# 6_-MCU_CONNECTORS.net
KiCad netlist of a schematic drawn in Altium Designer
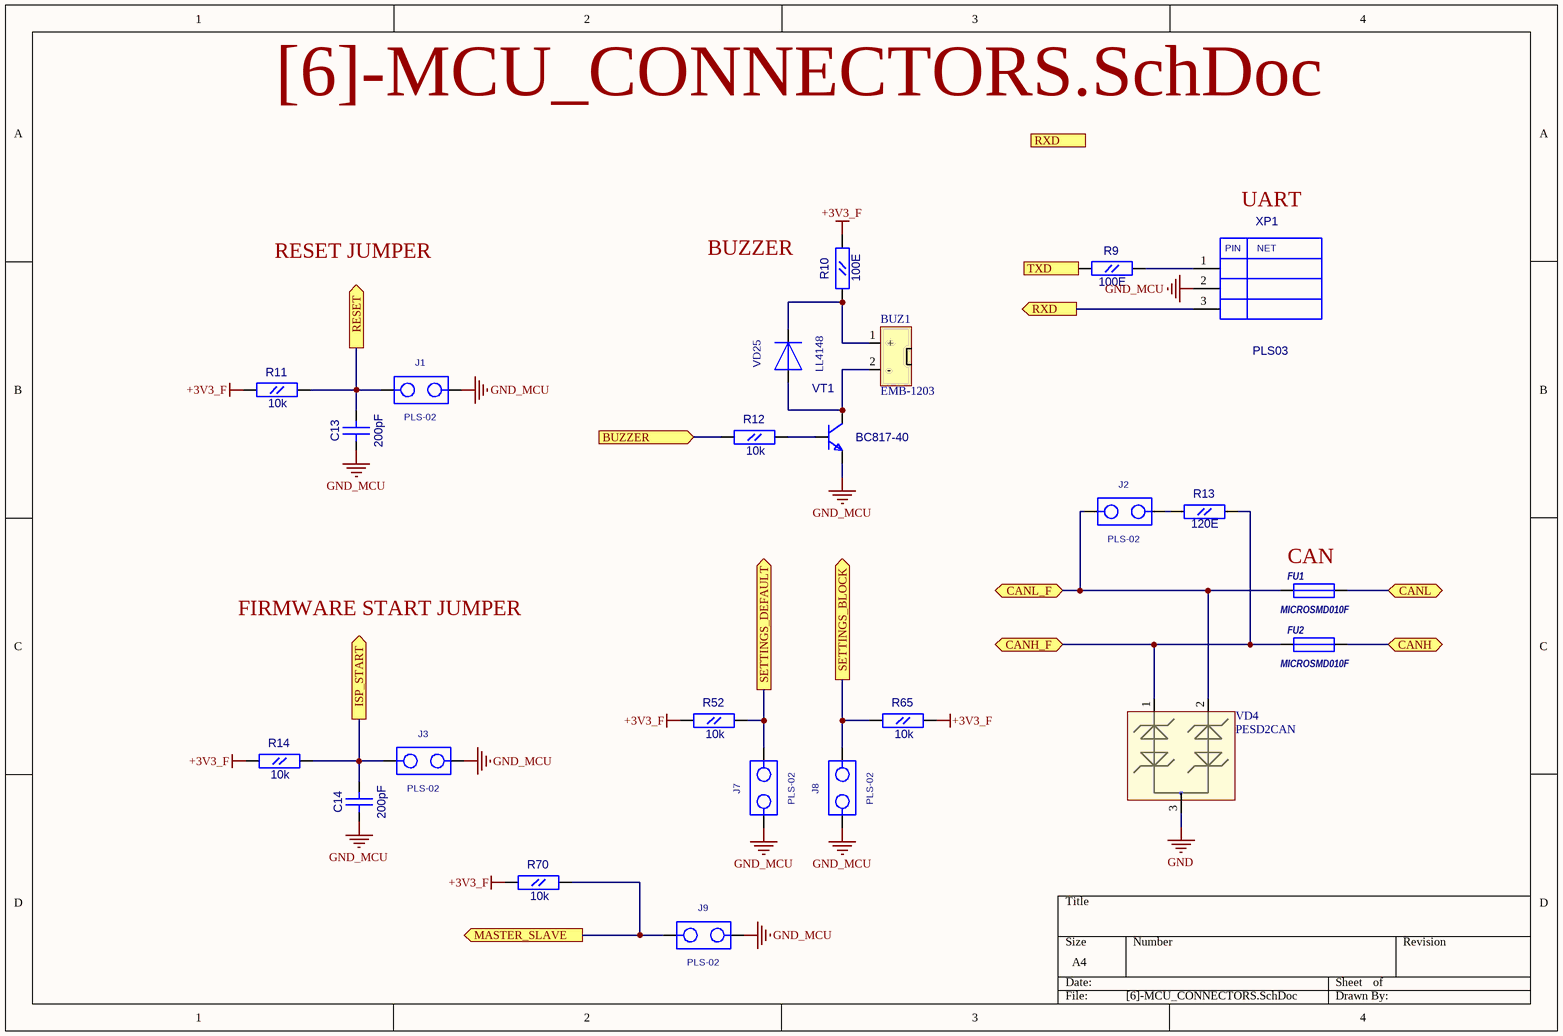
[diagram p0: [6]-MCU_CONNECTORS.SchDoc]

(export (version "E")
  (design (tool "Eeschema 10.0.6"))
  (components
    (comp (ref "BUZ1")
      (value "EMB-1203")
      (footprint "BUZZER_12")
      (description "Buzzer diameter 12mm 3V")
      (libsource (lib "fizik_lib") (part "EMB-1203"))
    )
    (comp (ref "C13")
      (value "200pF")
      (footprint "CC0603")
      (description "CC0603")
      (libsource (lib "gprs_modem_2") (part "CC0603"))
    )
    (comp (ref "C14")
      (value "200pF")
      (footprint "CC0603")
      (description "CC0603")
      (libsource (lib "gprs_modem_2") (part "CC0603"))
    )
    (comp (ref "FU1")
      (value "MICROSMD010F")
      (footprint "RC1210")
      (description "MICROSMD")
      (libsource (lib "gprs_modem_2") (part "MICROSMD"))
    )
    (comp (ref "FU2")
      (value "MICROSMD010F")
      (footprint "RC1210")
      (description "MICROSMD")
      (libsource (lib "gprs_modem_2") (part "MICROSMD"))
    )
    (comp (ref "J1") (value "PLS-02") (footprint "PLS-02") (libsource (lib "gprs_modem_2") (part "PLS-02")))
    (comp (ref "J2") (value "PLS-02") (footprint "PLS-02") (libsource (lib "fizik_lib") (part "PLS-02")))
    (comp (ref "J3") (value "PLS-02") (footprint "PLS-02") (libsource (lib "gprs_modem_2") (part "PLS-02")))
    (comp (ref "J7") (value "PLS-02") (footprint "PLS-02") (libsource (lib "gprs_modem_2") (part "PLS-02")))
    (comp (ref "J8") (value "PLS-02") (footprint "PLS-02") (libsource (lib "gprs_modem_2") (part "PLS-02")))
    (comp (ref "J9") (value "PLS-02") (footprint "PLS-02") (libsource (lib "gprs_modem_2") (part "PLS-02")))
    (comp (ref "R9")
      (value "100E")
      (footprint "RC0603")
      (description "RC0603")
      (libsource (lib "gprs_modem_2") (part "RC0603"))
    )
    (comp (ref "R10")
      (value "100E")
      (footprint "RC0603")
      (description "RC0603")
      (libsource (lib "gprs_modem_2") (part "RC0603"))
    )
    (comp (ref "R11")
      (value "10k")
      (footprint "RC0603")
      (description "RC0603")
      (libsource (lib "gprs_modem_2") (part "RC0603"))
    )
    (comp (ref "R12")
      (value "10k")
      (footprint "RC0603")
      (description "RC0603")
      (libsource (lib "gprs_modem_2") (part "RC0603"))
    )
    (comp (ref "R13")
      (value "120E")
      (footprint "RC0805")
      (description "RC0805")
      (libsource (lib "fizik_lib") (part "RC0805"))
    )
    (comp (ref "R14")
      (value "10k")
      (footprint "RC0603")
      (description "RC0603")
      (libsource (lib "gprs_modem_2") (part "RC0603"))
    )
    (comp (ref "R52")
      (value "10k")
      (footprint "RC0603")
      (description "RC0603")
      (libsource (lib "gprs_modem_2") (part "RC0603"))
    )
    (comp (ref "R65")
      (value "10k")
      (footprint "RC0603")
      (description "RC0603")
      (libsource (lib "gprs_modem_2") (part "RC0603"))
    )
    (comp (ref "R70")
      (value "10k")
      (footprint "RC0603")
      (description "RC0603")
      (libsource (lib "gprs_modem_2") (part "RC0603"))
    )
    (comp (ref "VD4")
      (value "PESD2CAN")
      (footprint "SOT-23(123)")
      (description "TVS for CAN")
      (libsource (lib "gprs_modem_2") (part "PESD2CAN"))
    )
    (comp (ref "VD25") (value "LL4148") (footprint "SOD-80") (libsource (lib "fizik_lib") (part "LL4148")))
    (comp (ref "VT1")
      (value "BC817-40")
      (footprint "SOT-23(123)")
      (description "NPN 500ma transistor")
      (libsource (lib "fizik_lib") (part "BC846BLT1"))
    )
    (comp (ref "XP1") (value "PLS03") (footprint "PLS-03") (libsource (lib "fizik_lib") (part "PLS03")))
  )
  (nets
    (net (code "1") (name "+3V3_F") (class "Default")
      (node (ref "R10") (pin "2") (pinfunction "B_2") (pintype "passive"))
      (node (ref "R11") (pin "1") (pinfunction "A_1") (pintype "passive"))
      (node (ref "R14") (pin "1") (pinfunction "A_1") (pintype "passive"))
      (node (ref "R52") (pin "1") (pinfunction "A_1") (pintype "passive"))
      (node (ref "R65") (pin "2") (pinfunction "B_2") (pintype "passive"))
      (node (ref "R70") (pin "1") (pinfunction "A_1") (pintype "passive"))
    )
    (net (code "2") (name "/BUZZER") (class "Default")
      (node (ref "R12") (pin "1") (pinfunction "A_1") (pintype "passive"))
    )
    (net (code "3") (name "/CANH") (class "Default") (node (ref "FU2") (pin "2") (pintype "passive")))
    (net (code "4") (name "/CANH_F") (class "Default")
      (node (ref "FU2") (pin "1") (pintype "passive"))
      (node (ref "R13") (pin "2") (pinfunction "B_2") (pintype "passive"))
      (node (ref "VD4") (pin "1") (pinfunction "1_1") (pintype "passive"))
    )
    (net (code "5") (name "/CANL") (class "Default") (node (ref "FU1") (pin "2") (pintype "passive")))
    (net (code "6") (name "/CANL_F") (class "Default")
      (node (ref "FU1") (pin "1") (pintype "passive"))
      (node (ref "J2") (pin "1") (pintype "passive"))
      (node (ref "VD4") (pin "2") (pinfunction "2_2") (pintype "passive"))
    )
    (net (code "7") (name "/ISP_START") (class "Default")
      (node (ref "C14") (pin "2") (pinfunction "B_2") (pintype "passive"))
      (node (ref "J3") (pin "1") (pintype "passive"))
      (node (ref "R14") (pin "2") (pinfunction "B_2") (pintype "passive"))
    )
    (net (code "8") (name "/MASTER_SLAVE") (class "Default")
      (node (ref "J9") (pin "1") (pintype "passive"))
      (node (ref "R70") (pin "2") (pinfunction "B_2") (pintype "passive"))
    )
    (net (code "9") (name "/RESET") (class "Default")
      (node (ref "C13") (pin "2") (pinfunction "B_2") (pintype "passive"))
      (node (ref "J1") (pin "1") (pintype "passive"))
      (node (ref "R11") (pin "2") (pinfunction "B_2") (pintype "passive"))
    )
    (net (code "10") (name "/RXD") (class "Default")
      (node (ref "XP1") (pin "3") (pinfunction "3_3") (pintype "passive"))
    )
    (net (code "11") (name "/SETTINGS_BLOCK") (class "Default")
      (node (ref "J8") (pin "2") (pintype "passive"))
      (node (ref "R65") (pin "1") (pinfunction "A_1") (pintype "passive"))
    )
    (net (code "12") (name "/SETTINGS_DEFAULT") (class "Default")
      (node (ref "J7") (pin "2") (pintype "passive"))
      (node (ref "R52") (pin "2") (pinfunction "B_2") (pintype "passive"))
    )
    (net (code "13") (name "/TXD") (class "Default")
      (node (ref "R9") (pin "1") (pinfunction "A_1") (pintype "passive"))
    )
    (net (code "14") (name "GND") (class "Default")
      (node (ref "VD4") (pin "3") (pinfunction "3_3") (pintype "passive"))
    )
    (net (code "15") (name "GND_MCU") (class "Default")
      (node (ref "C13") (pin "1") (pinfunction "A_1") (pintype "passive"))
      (node (ref "C14") (pin "1") (pinfunction "A_1") (pintype "passive"))
      (node (ref "J1") (pin "2") (pintype "passive"))
      (node (ref "J3") (pin "2") (pintype "passive"))
      (node (ref "J7") (pin "1") (pintype "passive"))
      (node (ref "J8") (pin "1") (pintype "passive"))
      (node (ref "J9") (pin "2") (pintype "passive"))
      (node (ref "VT1") (pin "2") (pinfunction "E_2") (pintype "passive"))
      (node (ref "XP1") (pin "2") (pinfunction "2_2") (pintype "passive"))
    )
    (net (code "16") (name "Net-(BUZ1-+)") (class "Default")
      (node (ref "BUZ1") (pin "1") (pinfunction "+_1") (pintype "passive"))
      (node (ref "R10") (pin "1") (pinfunction "A_1") (pintype "passive"))
      (node (ref "VD25") (pin "2") (pinfunction "+_2") (pintype "passive"))
    )
    (net (code "17") (name "Net-(BUZ1--)") (class "Default")
      (node (ref "BUZ1") (pin "2") (pinfunction "-_2") (pintype "passive"))
      (node (ref "VD25") (pin "1") (pinfunction "-_1") (pintype "passive"))
      (node (ref "VT1") (pin "3") (pinfunction "C_3") (pintype "passive"))
    )
    (net (code "18") (name "Net-(R9-B)") (class "Default")
      (node (ref "R9") (pin "2") (pinfunction "B_2") (pintype "passive"))
      (node (ref "XP1") (pin "1") (pinfunction "1_1") (pintype "passive"))
    )
    (net (code "19") (name "Net-(R12-B)") (class "Default")
      (node (ref "R12") (pin "2") (pinfunction "B_2") (pintype "passive"))
      (node (ref "VT1") (pin "1") (pinfunction "B_1") (pintype "passive"))
    )
    (net (code "20") (name "Net-(R13-A)") (class "Default")
      (node (ref "J2") (pin "2") (pintype "passive"))
      (node (ref "R13") (pin "1") (pinfunction "A_1") (pintype "passive"))
    )
  )
)
